# Industrial-Controller_Power.net
KiCad netlist of a schematic drawn in Altium Designer
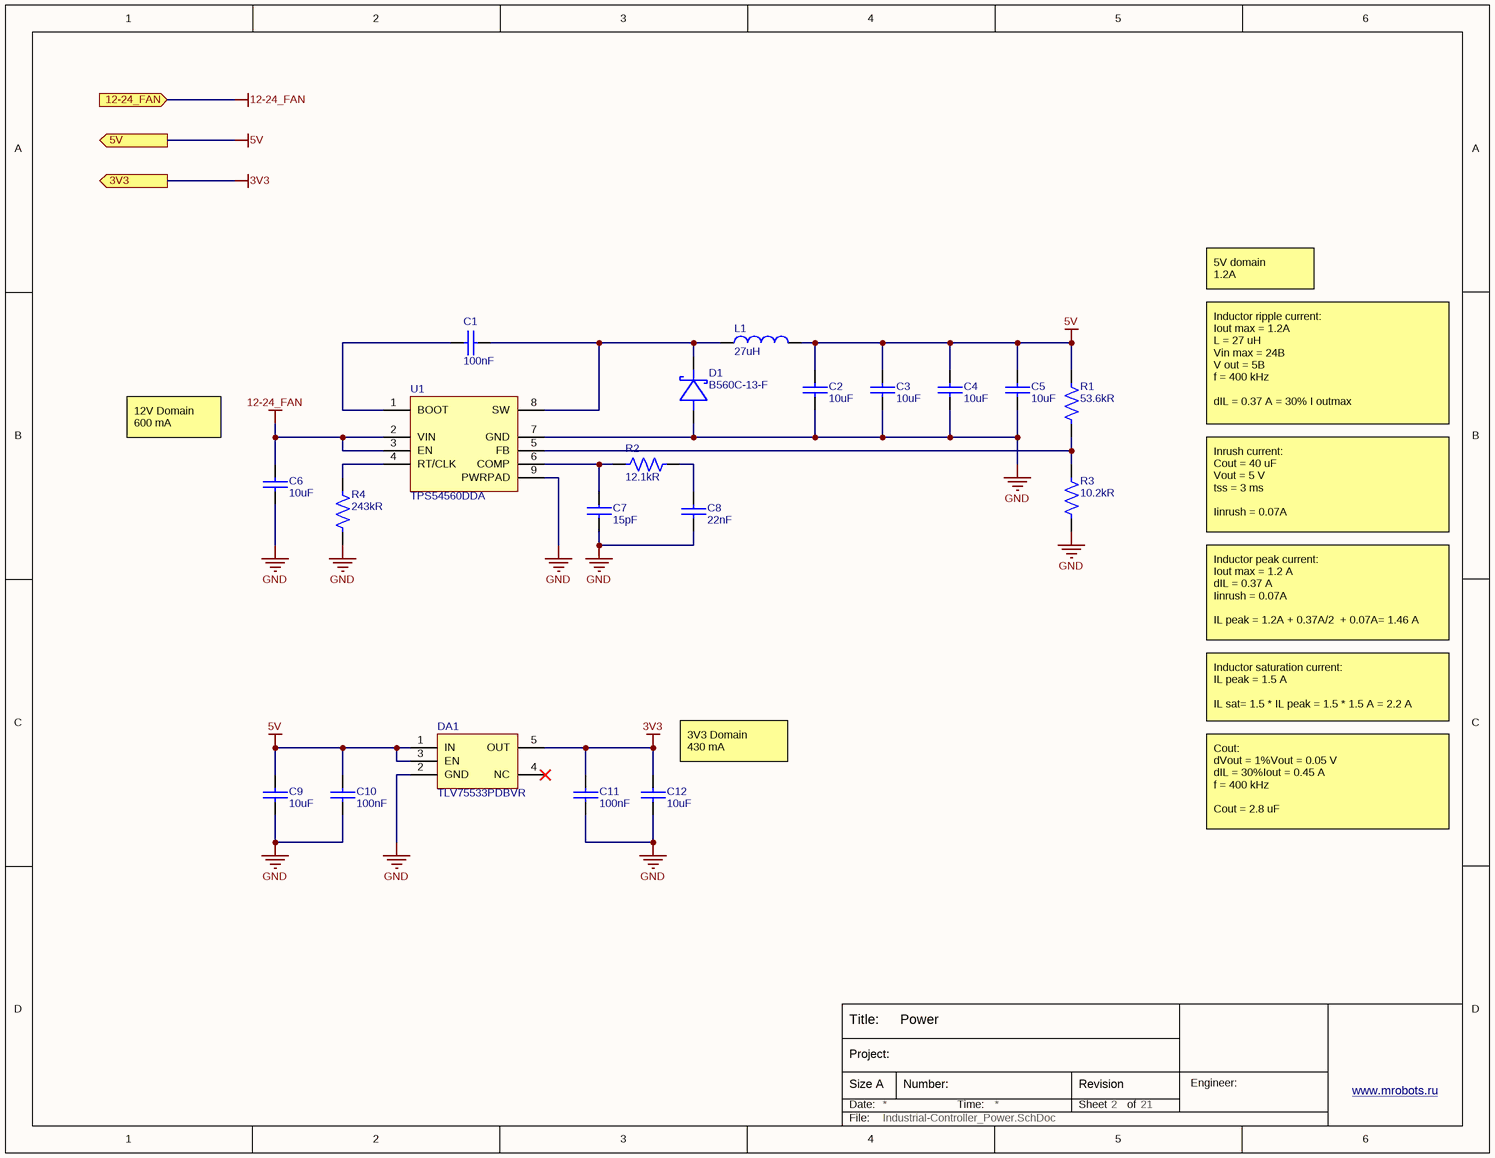
[diagram p0: Industrial-Controller_Power.SchDoc]

(export (version "E")
  (design (tool "Eeschema 10.0.6"))
  (components
    (comp (ref "C1")
      (value "100nF")
      (footprint "CAP_0603")
      (description "CAP CER 0.1UF 50V X7R 0603")
      (fields (field (name "TOLERANCE") "10%"))
      (libsource (lib "Industrial-Controller") (part "CL10B104KB8NNNL"))
    )
    (comp (ref "C2")
      (value "10uF")
      (footprint "CAP_1210")
      (description "CAP CER 10UF 50V X7R 1210")
      (fields (field (name "TOLERANCE") "10%"))
      (libsource (lib "Industrial-Controller") (part "CL32B106KBJNNWE"))
    )
    (comp (ref "C3")
      (value "10uF")
      (footprint "CAP_1210")
      (description "CAP CER 10UF 50V X7R 1210")
      (fields (field (name "TOLERANCE") "10%"))
      (libsource (lib "Industrial-Controller") (part "CL32B106KBJNNWE"))
    )
    (comp (ref "C4")
      (value "10uF")
      (footprint "CAP_1210")
      (description "CAP CER 10UF 50V X7R 1210")
      (fields (field (name "TOLERANCE") "10%"))
      (libsource (lib "Industrial-Controller") (part "CL32B106KBJNNWE"))
    )
    (comp (ref "C5")
      (value "10uF")
      (footprint "CAP_1210")
      (description "CAP CER 10UF 50V X7R 1210")
      (fields (field (name "TOLERANCE") "10%"))
      (libsource (lib "Industrial-Controller") (part "CL32B106KBJNNWE"))
    )
    (comp (ref "C6")
      (value "10uF")
      (footprint "CAP_1210")
      (description "CAP CER 10UF 50V X7R 1210")
      (fields (field (name "TOLERANCE") "10%"))
      (libsource (lib "Industrial-Controller") (part "CL32B106KBJNNWE"))
    )
    (comp (ref "C7")
      (value "15pF")
      (footprint "CAP_0603")
      (description "CAP CER 15PF 50V C0G/NP0 0603")
      (fields (field (name "TOLERANCE") "5%") (field (name "VOLTAGE") "50V"))
      (libsource (lib "Industrial-Controller") (part "C0603C150J5GAC7867"))
    )
    (comp (ref "C8")
      (value "22nF")
      (footprint "CAP_0603")
      (description "CAP CER 0.022UF 50V X7R 0603")
      (fields (field (name "TOLERANCE") "10%") (field (name "VOLTAGE") "50V"))
      (libsource (lib "Industrial-Controller") (part "CC0603KRX7R9BB223"))
    )
    (comp (ref "C9")
      (value "10uF")
      (footprint "CAP_1210")
      (description "CAP CER 10UF 50V X7R 1210")
      (fields (field (name "TOLERANCE") "10%"))
      (libsource (lib "Industrial-Controller") (part "CL32B106KBJNNWE"))
    )
    (comp (ref "C10")
      (value "100nF")
      (footprint "CAP_0603")
      (description "CAP CER 0.1UF 50V X7R 0603")
      (fields (field (name "TOLERANCE") "10%"))
      (libsource (lib "Industrial-Controller") (part "CL10B104KB8NNNL"))
    )
    (comp (ref "C11")
      (value "100nF")
      (footprint "CAP_0603")
      (description "CAP CER 0.1UF 50V X7R 0603")
      (fields (field (name "TOLERANCE") "10%"))
      (libsource (lib "Industrial-Controller") (part "CL10B104KB8NNNL"))
    )
    (comp (ref "C12")
      (value "10uF")
      (footprint "CAP_1210")
      (description "CAP CER 10UF 50V X7R 1210")
      (fields (field (name "TOLERANCE") "10%"))
      (libsource (lib "Industrial-Controller") (part "CL32B106KBJNNWE"))
    )
    (comp (ref "D1")
      (value "B560C-13-F")
      (footprint "SMC")
      (description "DIODE SCHOTTKY 60V 5A SMC")
      (libsource (lib "Industrial-Controller") (part "B560C-13-F"))
    )
    (comp (ref "DA1")
      (value "TLV75533PDBVR")
      (footprint "SOT-23-5")
      (description "IC REG LINEAR 3.3V 500MA SOT23-5")
      (libsource (lib "Industrial-Controller") (part "TLV75533PDBVR"))
    )
    (comp (ref "L1")
      (value "27uH")
      (footprint "SDR1006")
      (description "FIXED IND 27UH 1.75A 110MOHM SMD")
      (fields (field (name "TOLERANCE") "10%"))
      (libsource (lib "Industrial-Controller") (part "SDR1006-270KL"))
    )
    (comp (ref "R1")
      (value "53.6kR")
      (footprint "RES_0603")
      (description "RES 53.6K OHM 1% 1/10W 0603")
      (fields (field (name "TOLERANCE") "1%"))
      (libsource (lib "Industrial-Controller") (part "RC0603FR-0753K6L"))
    )
    (comp (ref "R2")
      (value "12.1kR")
      (footprint "RES_0603")
      (description "RES 12.1K OHM 1% 1/10W 0603")
      (fields (field (name "TOLERANCE") "1%"))
      (libsource (lib "Industrial-Controller") (part "RC0603FR-0712K1L"))
    )
    (comp (ref "R3")
      (value "10.2kR")
      (footprint "RES_0603")
      (description "RES 10.2K OHM 1% 1/10W 0603")
      (fields (field (name "TOLERANCE") "1%"))
      (libsource (lib "Industrial-Controller") (part "RC0603FR-0710K2L"))
    )
    (comp (ref "R4")
      (value "243kR")
      (footprint "RES_0603")
      (description "RES 243K OHM 1% 1/10W 0603")
      (fields (field (name "TOLERANCE") "1%"))
      (libsource (lib "Industrial-Controller") (part "RC0603FR-07243KL"))
    )
    (comp (ref "U1")
      (value "TPS54560DDA")
      (footprint "SOIC-8EP_150mil")
      (description "IC REG BCK SPLIT RAIL ADJ 8SOPWR")
      (libsource (lib "Industrial-Controller") (part "TPS54560DDA"))
    )
  )
  (nets
    (net (code "1") (name "3V3") (class "Default")
      (node (ref "C11") (pin "1") (pinfunction "1_1") (pintype "passive"))
      (node (ref "C12") (pin "2") (pinfunction "2_2") (pintype "passive"))
      (node (ref "DA1") (pin "5") (pinfunction "OUT_5") (pintype "passive"))
    )
    (net (code "2") (name "5V") (class "Default")
      (node (ref "C10") (pin "1") (pinfunction "1_1") (pintype "passive"))
      (node (ref "C2") (pin "2") (pinfunction "2_2") (pintype "passive"))
      (node (ref "C3") (pin "2") (pinfunction "2_2") (pintype "passive"))
      (node (ref "C4") (pin "2") (pinfunction "2_2") (pintype "passive"))
      (node (ref "C5") (pin "2") (pinfunction "2_2") (pintype "passive"))
      (node (ref "C9") (pin "2") (pinfunction "2_2") (pintype "passive"))
      (node (ref "DA1") (pin "1") (pinfunction "IN_1") (pintype "passive"))
      (node (ref "DA1") (pin "3") (pinfunction "EN_3") (pintype "passive"))
      (node (ref "L1") (pin "2") (pinfunction "2_2") (pintype "passive"))
      (node (ref "R1") (pin "1") (pinfunction "1_1") (pintype "passive"))
    )
    (net (code "3") (name "12-24_FAN") (class "Default")
      (node (ref "C6") (pin "2") (pinfunction "2_2") (pintype "passive"))
      (node (ref "U1") (pin "2") (pinfunction "VIN_2") (pintype "passive"))
      (node (ref "U1") (pin "3") (pinfunction "EN_3") (pintype "passive"))
    )
    (net (code "4") (name "GND") (class "Default")
      (node (ref "C10") (pin "2") (pinfunction "2_2") (pintype "passive"))
      (node (ref "C11") (pin "2") (pinfunction "2_2") (pintype "passive"))
      (node (ref "C12") (pin "1") (pinfunction "1_1") (pintype "passive"))
      (node (ref "C2") (pin "1") (pinfunction "1_1") (pintype "passive"))
      (node (ref "C3") (pin "1") (pinfunction "1_1") (pintype "passive"))
      (node (ref "C4") (pin "1") (pinfunction "1_1") (pintype "passive"))
      (node (ref "C5") (pin "1") (pinfunction "1_1") (pintype "passive"))
      (node (ref "C6") (pin "1") (pinfunction "1_1") (pintype "passive"))
      (node (ref "C7") (pin "2") (pinfunction "2_2") (pintype "passive"))
      (node (ref "C8") (pin "1") (pinfunction "1_1") (pintype "passive"))
      (node (ref "C9") (pin "1") (pinfunction "1_1") (pintype "passive"))
      (node (ref "D1") (pin "2") (pinfunction "A_2") (pintype "passive"))
      (node (ref "DA1") (pin "2") (pinfunction "GND_2") (pintype "power_in"))
      (node (ref "R3") (pin "2") (pinfunction "2_2") (pintype "passive"))
      (node (ref "R4") (pin "2") (pinfunction "2_2") (pintype "passive"))
      (node (ref "U1") (pin "7") (pinfunction "GND_7") (pintype "passive"))
      (node (ref "U1") (pin "9") (pinfunction "PWRPAD_9") (pintype "passive"))
    )
    (net (code "5") (name "Net-(C8-Pad2)") (class "Default")
      (node (ref "C8") (pin "2") (pinfunction "2_2") (pintype "passive"))
      (node (ref "R2") (pin "2") (pinfunction "2_2") (pintype "passive"))
    )
    (net (code "6") (name "Net-(D1-C)") (class "Default")
      (node (ref "C1") (pin "2") (pinfunction "2_2") (pintype "passive"))
      (node (ref "D1") (pin "1") (pinfunction "C_1") (pintype "passive"))
      (node (ref "L1") (pin "1") (pinfunction "1_1") (pintype "passive"))
      (node (ref "U1") (pin "8") (pinfunction "SW_8") (pintype "passive"))
    )
    (net (code "7") (name "Net-(U1-BOOT)") (class "Default")
      (node (ref "C1") (pin "1") (pinfunction "1_1") (pintype "passive"))
      (node (ref "U1") (pin "1") (pinfunction "BOOT_1") (pintype "passive"))
    )
    (net (code "8") (name "Net-(U1-COMP)") (class "Default")
      (node (ref "C7") (pin "1") (pinfunction "1_1") (pintype "passive"))
      (node (ref "R2") (pin "1") (pinfunction "1_1") (pintype "passive"))
      (node (ref "U1") (pin "6") (pinfunction "COMP_6") (pintype "passive"))
    )
    (net (code "9") (name "Net-(U1-FB)") (class "Default")
      (node (ref "R1") (pin "2") (pinfunction "2_2") (pintype "passive"))
      (node (ref "R3") (pin "1") (pinfunction "1_1") (pintype "passive"))
      (node (ref "U1") (pin "5") (pinfunction "FB_5") (pintype "passive"))
    )
    (net (code "10") (name "Net-(U1-RT{slash}CLK)") (class "Default")
      (node (ref "R4") (pin "1") (pinfunction "1_1") (pintype "passive"))
      (node (ref "U1") (pin "4") (pinfunction "RT/CLK_4") (pintype "passive"))
    )
    (net (code "11") (name "unconnected-(DA1-NC-Pad4)") (class "Default")
      (node (ref "DA1") (pin "4") (pinfunction "NC_4") (pintype "power_in+no_connect"))
    )
  )
)
